# sch.net
KiCad netlist of a schematic drawn in Altium Designer
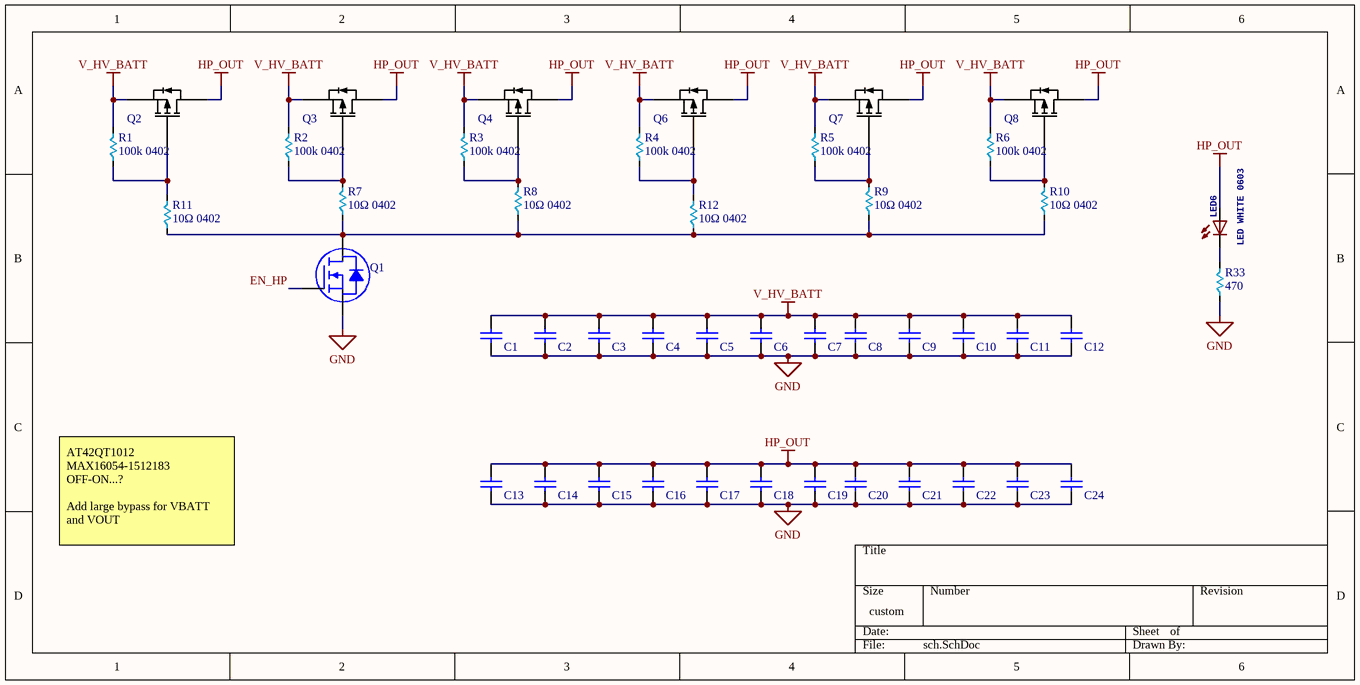
[diagram p0: sch.SchDoc]

(export (version "E")
  (design (tool "Eeschema 10.0.6"))
  (components
    (comp (ref "C1")
      (value "22uF")
      (footprint "C1210")
      (description "22uF 1206")
      (libsource (lib "RLC") (part "C-22uF-1206"))
    )
    (comp (ref "C2")
      (value "22uF")
      (footprint "C1210")
      (description "22uF 1206")
      (libsource (lib "RLC") (part "C-22uF-1206"))
    )
    (comp (ref "C3")
      (value "22uF")
      (footprint "C1210")
      (description "22uF 1206")
      (libsource (lib "RLC") (part "C-22uF-1206"))
    )
    (comp (ref "C4")
      (value "22uF")
      (footprint "C1210")
      (description "22uF 1206")
      (libsource (lib "RLC") (part "C-22uF-1206"))
    )
    (comp (ref "C5")
      (value "22uF")
      (footprint "C1210")
      (description "22uF 1206")
      (libsource (lib "RLC") (part "C-22uF-1206"))
    )
    (comp (ref "C6")
      (value "22uF")
      (footprint "C1210")
      (description "22uF 1206")
      (libsource (lib "RLC") (part "C-22uF-1206"))
    )
    (comp (ref "C7")
      (value "22uF")
      (footprint "C1210")
      (description "22uF 1206")
      (libsource (lib "RLC") (part "C-22uF-1206"))
    )
    (comp (ref "C8")
      (value "22uF")
      (footprint "C1210")
      (description "22uF 1206")
      (libsource (lib "RLC") (part "C-22uF-1206"))
    )
    (comp (ref "C9")
      (value "22uF")
      (footprint "C1210")
      (description "22uF 1206")
      (libsource (lib "RLC") (part "C-22uF-1206"))
    )
    (comp (ref "C10")
      (value "22uF")
      (footprint "C1210")
      (description "22uF 1206")
      (libsource (lib "RLC") (part "C-22uF-1206"))
    )
    (comp (ref "C11")
      (value "22uF")
      (footprint "C1210")
      (description "22uF 1206")
      (libsource (lib "RLC") (part "C-22uF-1206"))
    )
    (comp (ref "C12")
      (value "22uF")
      (footprint "C1210")
      (description "22uF 1206")
      (libsource (lib "RLC") (part "C-22uF-1206"))
    )
    (comp (ref "C13")
      (value "22uF")
      (footprint "C1210")
      (description "22uF 1206")
      (libsource (lib "RLC") (part "C-22uF-1206"))
    )
    (comp (ref "C14")
      (value "22uF")
      (footprint "C1210")
      (description "22uF 1206")
      (libsource (lib "RLC") (part "C-22uF-1206"))
    )
    (comp (ref "C15")
      (value "22uF")
      (footprint "C1210")
      (description "22uF 1206")
      (libsource (lib "RLC") (part "C-22uF-1206"))
    )
    (comp (ref "C16")
      (value "22uF")
      (footprint "C1210")
      (description "22uF 1206")
      (libsource (lib "RLC") (part "C-22uF-1206"))
    )
    (comp (ref "C17")
      (value "22uF")
      (footprint "C1210")
      (description "22uF 1206")
      (libsource (lib "RLC") (part "C-22uF-1206"))
    )
    (comp (ref "C18")
      (value "22uF")
      (footprint "C1210")
      (description "22uF 1206")
      (libsource (lib "RLC") (part "C-22uF-1206"))
    )
    (comp (ref "C19")
      (value "22uF")
      (footprint "C1210")
      (description "22uF 1206")
      (libsource (lib "RLC") (part "C-22uF-1206"))
    )
    (comp (ref "C20")
      (value "22uF")
      (footprint "C1210")
      (description "22uF 1206")
      (libsource (lib "RLC") (part "C-22uF-1206"))
    )
    (comp (ref "C21")
      (value "22uF")
      (footprint "C1210")
      (description "22uF 1206")
      (libsource (lib "RLC") (part "C-22uF-1206"))
    )
    (comp (ref "C22")
      (value "22uF")
      (footprint "C1210")
      (description "22uF 1206")
      (libsource (lib "RLC") (part "C-22uF-1206"))
    )
    (comp (ref "C23")
      (value "22uF")
      (footprint "C1210")
      (description "22uF 1206")
      (libsource (lib "RLC") (part "C-22uF-1206"))
    )
    (comp (ref "C24")
      (value "22uF")
      (footprint "C1210")
      (description "22uF 1206")
      (libsource (lib "RLC") (part "C-22uF-1206"))
    )
    (comp (ref "LED6")
      (value "LED WHITE 0603")
      (footprint "LED_0603")
      (description "LED   Source: http://www.osram.convergy.de   Source: www.luxeon.com   Source: www.kingbright.com")
      (fields
        (field (name "MANUFACTURER") "Dialight")
        (field (name "MANUFACTURER PART NUMBER") "5988070107F")
      )
      (libsource (lib "solidstate-power") (part "LED_ESML0603"))
    )
    (comp (ref "Q1")
      (value "HP-MOS")
      (footprint "VSON-8-NFET")
      (fields
        (field (name "MANUFACTURER") "Alpha & Omega Semiconductor")
        (field (name "MANUFACTURER PART NUMBER") "AON7400B")
      )
      (libsource (lib "solidstate-power") (part "N-MOS"))
    )
    (comp (ref "Q2")
      (value "High power mosfet")
      (footprint "DPAK")
      (libsource (lib "robot-cortex") (part "P-MOS-DPAK"))
    )
    (comp (ref "Q3")
      (value "High power mosfet")
      (footprint "DPAK")
      (libsource (lib "robot-cortex") (part "P-MOS-DPAK"))
    )
    (comp (ref "Q4")
      (value "High power mosfet")
      (footprint "DPAK")
      (libsource (lib "robot-cortex") (part "P-MOS-DPAK"))
    )
    (comp (ref "Q6")
      (value "High power mosfet")
      (footprint "DPAK")
      (libsource (lib "robot-cortex") (part "P-MOS-DPAK"))
    )
    (comp (ref "Q7")
      (value "High power mosfet")
      (footprint "DPAK")
      (libsource (lib "robot-cortex") (part "P-MOS-DPAK"))
    )
    (comp (ref "Q8")
      (value "High power mosfet")
      (footprint "DPAK")
      (libsource (lib "robot-cortex") (part "P-MOS-DPAK"))
    )
    (comp (ref "R1") (value "100k 0402") (footprint "R0402") (libsource (lib "RLC") (part "R-100k-0402")))
    (comp (ref "R2") (value "100k 0402") (footprint "R0402") (libsource (lib "RLC") (part "R-100k-0402")))
    (comp (ref "R3") (value "100k 0402") (footprint "R0402") (libsource (lib "RLC") (part "R-100k-0402")))
    (comp (ref "R4") (value "100k 0402") (footprint "R0402") (libsource (lib "RLC") (part "R-100k-0402")))
    (comp (ref "R5") (value "100k 0402") (footprint "R0402") (libsource (lib "RLC") (part "R-100k-0402")))
    (comp (ref "R6") (value "100k 0402") (footprint "R0402") (libsource (lib "RLC") (part "R-100k-0402")))
    (comp (ref "R7") (value "10Ω 0402") (footprint "R0402") (libsource (lib "RLC") (part "R-10-0402")))
    (comp (ref "R8") (value "10Ω 0402") (footprint "R0402") (libsource (lib "RLC") (part "R-10-0402")))
    (comp (ref "R9") (value "10Ω 0402") (footprint "R0402") (libsource (lib "RLC") (part "R-10-0402")))
    (comp (ref "R10") (value "10Ω 0402") (footprint "R0402") (libsource (lib "RLC") (part "R-10-0402")))
    (comp (ref "R11") (value "10Ω 0402") (footprint "R0402") (libsource (lib "RLC") (part "R-10-0402")))
    (comp (ref "R12") (value "10Ω 0402") (footprint "R0402") (libsource (lib "RLC") (part "R-10-0402")))
    (comp (ref "R33")
      (value "470")
      (footprint "R0402")
      (fields
        (field (name "MANUFACTURER") "Yageo")
        (field (name "MANUFACTURER PART NUMBER") "RC0402JR-07470RL")
        (field (name "TOLERANCE") "5%")
      )
      (libsource (lib "JC_sch") (part "R-470-0402"))
    )
  )
  (nets
    (net (code "1") (name "/EN_HP") (class "Default")
      (node (ref "Q1") (pin "G") (pinfunction "G_G") (pintype "passive"))
    )
    (net (code "2") (name "GND") (class "Default")
      (node (ref "C1") (pin "1") (pinfunction "1_1") (pintype "passive"))
      (node (ref "C10") (pin "1") (pinfunction "1_1") (pintype "passive"))
      (node (ref "C11") (pin "1") (pinfunction "1_1") (pintype "passive"))
      (node (ref "C12") (pin "1") (pinfunction "1_1") (pintype "passive"))
      (node (ref "C13") (pin "1") (pinfunction "1_1") (pintype "passive"))
      (node (ref "C14") (pin "1") (pinfunction "1_1") (pintype "passive"))
      (node (ref "C15") (pin "1") (pinfunction "1_1") (pintype "passive"))
      (node (ref "C16") (pin "1") (pinfunction "1_1") (pintype "passive"))
      (node (ref "C17") (pin "1") (pinfunction "1_1") (pintype "passive"))
      (node (ref "C18") (pin "1") (pinfunction "1_1") (pintype "passive"))
      (node (ref "C19") (pin "1") (pinfunction "1_1") (pintype "passive"))
      (node (ref "C2") (pin "1") (pinfunction "1_1") (pintype "passive"))
      (node (ref "C20") (pin "1") (pinfunction "1_1") (pintype "passive"))
      (node (ref "C21") (pin "1") (pinfunction "1_1") (pintype "passive"))
      (node (ref "C22") (pin "1") (pinfunction "1_1") (pintype "passive"))
      (node (ref "C23") (pin "1") (pinfunction "1_1") (pintype "passive"))
      (node (ref "C24") (pin "1") (pinfunction "1_1") (pintype "passive"))
      (node (ref "C3") (pin "1") (pinfunction "1_1") (pintype "passive"))
      (node (ref "C4") (pin "1") (pinfunction "1_1") (pintype "passive"))
      (node (ref "C5") (pin "1") (pinfunction "1_1") (pintype "passive"))
      (node (ref "C6") (pin "1") (pinfunction "1_1") (pintype "passive"))
      (node (ref "C7") (pin "1") (pinfunction "1_1") (pintype "passive"))
      (node (ref "C8") (pin "1") (pinfunction "1_1") (pintype "passive"))
      (node (ref "C9") (pin "1") (pinfunction "1_1") (pintype "passive"))
      (node (ref "Q1") (pin "S") (pinfunction "S_S") (pintype "passive"))
      (node (ref "R33") (pin "2") (pinfunction "2_2") (pintype "passive"))
    )
    (net (code "3") (name "HP_OUT") (class "Default")
      (node (ref "C13") (pin "2") (pinfunction "2_2") (pintype "passive"))
      (node (ref "C14") (pin "2") (pinfunction "2_2") (pintype "passive"))
      (node (ref "C15") (pin "2") (pinfunction "2_2") (pintype "passive"))
      (node (ref "C16") (pin "2") (pinfunction "2_2") (pintype "passive"))
      (node (ref "C17") (pin "2") (pinfunction "2_2") (pintype "passive"))
      (node (ref "C18") (pin "2") (pinfunction "2_2") (pintype "passive"))
      (node (ref "C19") (pin "2") (pinfunction "2_2") (pintype "passive"))
      (node (ref "C20") (pin "2") (pinfunction "2_2") (pintype "passive"))
      (node (ref "C21") (pin "2") (pinfunction "2_2") (pintype "passive"))
      (node (ref "C22") (pin "2") (pinfunction "2_2") (pintype "passive"))
      (node (ref "C23") (pin "2") (pinfunction "2_2") (pintype "passive"))
      (node (ref "C24") (pin "2") (pinfunction "2_2") (pintype "passive"))
      (node (ref "LED6") (pin "A") (pinfunction "A_A") (pintype "passive"))
      (node (ref "Q2") (pin "4") (pinfunction "D_4") (pintype "passive"))
      (node (ref "Q3") (pin "4") (pinfunction "D_4") (pintype "passive"))
      (node (ref "Q4") (pin "4") (pinfunction "D_4") (pintype "passive"))
      (node (ref "Q6") (pin "4") (pinfunction "D_4") (pintype "passive"))
      (node (ref "Q7") (pin "4") (pinfunction "D_4") (pintype "passive"))
      (node (ref "Q8") (pin "4") (pinfunction "D_4") (pintype "passive"))
    )
    (net (code "4") (name "Net-(LED6-PadC)") (class "Default")
      (node (ref "LED6") (pin "C") (pinfunction "C_C") (pintype "passive"))
      (node (ref "R33") (pin "1") (pinfunction "1_1") (pintype "passive"))
    )
    (net (code "5") (name "Net-(Q1-PadD)") (class "Default")
      (node (ref "Q1") (pin "D") (pinfunction "D_D") (pintype "passive"))
      (node (ref "R10") (pin "2") (pinfunction "2_2") (pintype "passive"))
      (node (ref "R11") (pin "2") (pinfunction "2_2") (pintype "passive"))
      (node (ref "R12") (pin "2") (pinfunction "2_2") (pintype "passive"))
      (node (ref "R7") (pin "2") (pinfunction "2_2") (pintype "passive"))
      (node (ref "R8") (pin "2") (pinfunction "2_2") (pintype "passive"))
      (node (ref "R9") (pin "2") (pinfunction "2_2") (pintype "passive"))
    )
    (net (code "6") (name "Net-(Q2-G)") (class "Default")
      (node (ref "Q2") (pin "1") (pinfunction "G_1") (pintype "passive"))
      (node (ref "R1") (pin "2") (pinfunction "2_2") (pintype "passive"))
      (node (ref "R11") (pin "1") (pinfunction "1_1") (pintype "passive"))
    )
    (net (code "7") (name "Net-(Q3-G)") (class "Default")
      (node (ref "Q3") (pin "1") (pinfunction "G_1") (pintype "passive"))
      (node (ref "R2") (pin "2") (pinfunction "2_2") (pintype "passive"))
      (node (ref "R7") (pin "1") (pinfunction "1_1") (pintype "passive"))
    )
    (net (code "8") (name "Net-(Q4-G)") (class "Default")
      (node (ref "Q4") (pin "1") (pinfunction "G_1") (pintype "passive"))
      (node (ref "R3") (pin "2") (pinfunction "2_2") (pintype "passive"))
      (node (ref "R8") (pin "1") (pinfunction "1_1") (pintype "passive"))
    )
    (net (code "9") (name "Net-(Q6-G)") (class "Default")
      (node (ref "Q6") (pin "1") (pinfunction "G_1") (pintype "passive"))
      (node (ref "R12") (pin "1") (pinfunction "1_1") (pintype "passive"))
      (node (ref "R4") (pin "2") (pinfunction "2_2") (pintype "passive"))
    )
    (net (code "10") (name "Net-(Q7-G)") (class "Default")
      (node (ref "Q7") (pin "1") (pinfunction "G_1") (pintype "passive"))
      (node (ref "R5") (pin "2") (pinfunction "2_2") (pintype "passive"))
      (node (ref "R9") (pin "1") (pinfunction "1_1") (pintype "passive"))
    )
    (net (code "11") (name "Net-(Q8-G)") (class "Default")
      (node (ref "Q8") (pin "1") (pinfunction "G_1") (pintype "passive"))
      (node (ref "R10") (pin "1") (pinfunction "1_1") (pintype "passive"))
      (node (ref "R6") (pin "2") (pinfunction "2_2") (pintype "passive"))
    )
    (net (code "12") (name "V_HV_BATT") (class "Default")
      (node (ref "C1") (pin "2") (pinfunction "2_2") (pintype "passive"))
      (node (ref "C10") (pin "2") (pinfunction "2_2") (pintype "passive"))
      (node (ref "C11") (pin "2") (pinfunction "2_2") (pintype "passive"))
      (node (ref "C12") (pin "2") (pinfunction "2_2") (pintype "passive"))
      (node (ref "C2") (pin "2") (pinfunction "2_2") (pintype "passive"))
      (node (ref "C3") (pin "2") (pinfunction "2_2") (pintype "passive"))
      (node (ref "C4") (pin "2") (pinfunction "2_2") (pintype "passive"))
      (node (ref "C5") (pin "2") (pinfunction "2_2") (pintype "passive"))
      (node (ref "C6") (pin "2") (pinfunction "2_2") (pintype "passive"))
      (node (ref "C7") (pin "2") (pinfunction "2_2") (pintype "passive"))
      (node (ref "C8") (pin "2") (pinfunction "2_2") (pintype "passive"))
      (node (ref "C9") (pin "2") (pinfunction "2_2") (pintype "passive"))
      (node (ref "Q2") (pin "3") (pinfunction "S_3") (pintype "passive"))
      (node (ref "Q3") (pin "3") (pinfunction "S_3") (pintype "passive"))
      (node (ref "Q4") (pin "3") (pinfunction "S_3") (pintype "passive"))
      (node (ref "Q6") (pin "3") (pinfunction "S_3") (pintype "passive"))
      (node (ref "Q7") (pin "3") (pinfunction "S_3") (pintype "passive"))
      (node (ref "Q8") (pin "3") (pinfunction "S_3") (pintype "passive"))
      (node (ref "R1") (pin "1") (pinfunction "1_1") (pintype "passive"))
      (node (ref "R2") (pin "1") (pinfunction "1_1") (pintype "passive"))
      (node (ref "R3") (pin "1") (pinfunction "1_1") (pintype "passive"))
      (node (ref "R4") (pin "1") (pinfunction "1_1") (pintype "passive"))
      (node (ref "R5") (pin "1") (pinfunction "1_1") (pintype "passive"))
      (node (ref "R6") (pin "1") (pinfunction "1_1") (pintype "passive"))
    )
  )
)
